# lt3652.net
KiCad netlist of a schematic drawn in EAGLE
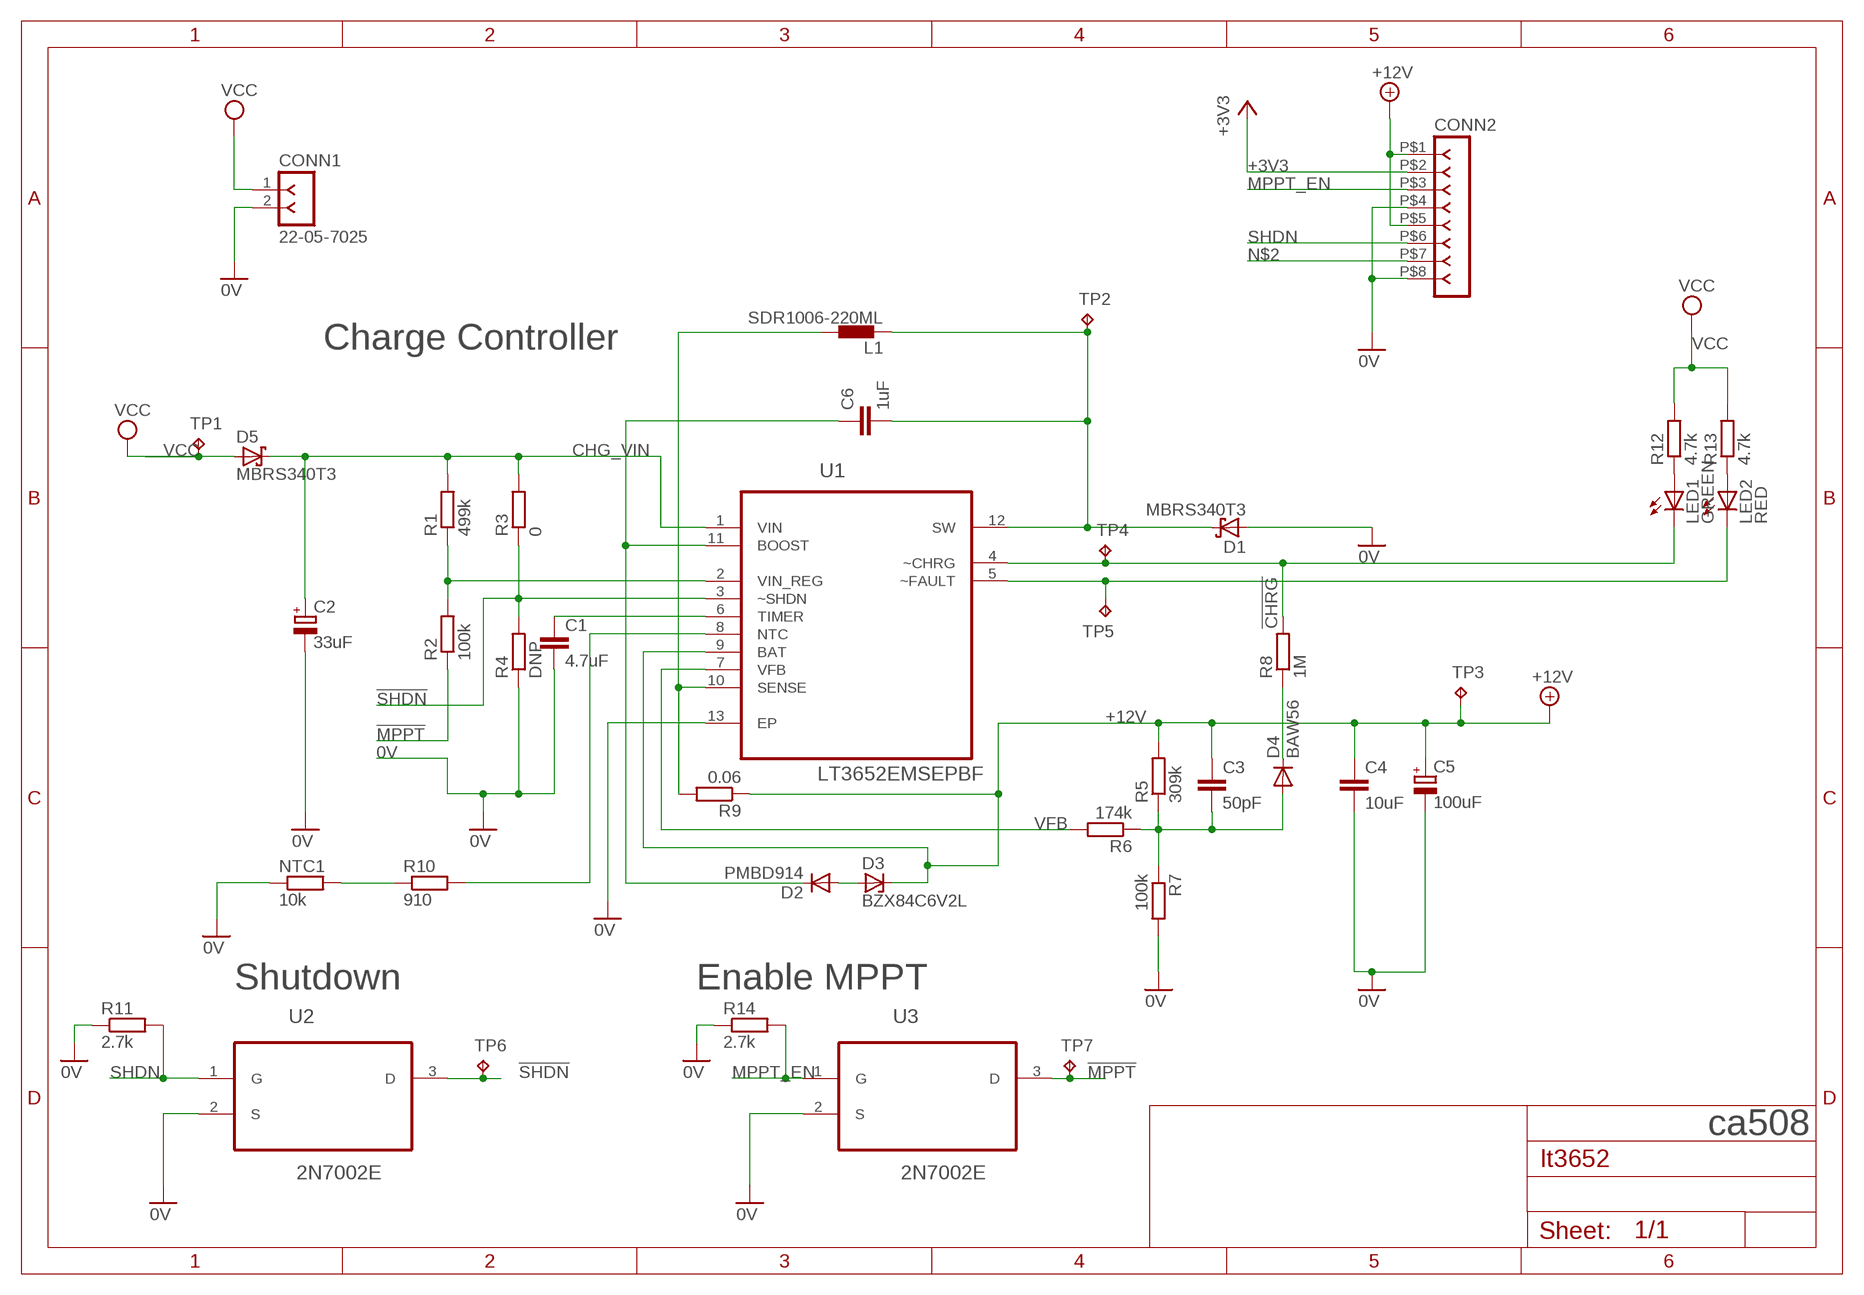
[diagram p0: schematic, sheet 1]

(export (version "E")
  (design (tool "Eeschema 10.0.6"))
  (components
    (comp (ref "C1")
      (value "4.7uF")
      (footprint "eagle-import:C1206")
      (libsource (lib "eagle-import") (part "C-EUC1206"))
    )
    (comp (ref "C2")
      (value "33uF")
      (footprint "eagle-import:PANASONIC_D")
      (libsource (lib "eagle-import") (part "CPOL-EUD"))
    )
    (comp (ref "C3")
      (value "50pF")
      (footprint "eagle-import:C0603")
      (libsource (lib "eagle-import") (part "C-EUC0603"))
    )
    (comp (ref "C4")
      (value "10uF")
      (footprint "eagle-import:C1206")
      (libsource (lib "eagle-import") (part "C-EUC1206"))
    )
    (comp (ref "C5")
      (value "100uF")
      (footprint "eagle-import:PANASONIC_F")
      (libsource (lib "eagle-import") (part "CPOL-EUF"))
    )
    (comp (ref "C6")
      (value "1uF")
      (footprint "eagle-import:C0805")
      (libsource (lib "eagle-import") (part "C-EUC0805"))
    )
    (comp (ref "CONN1")
      (value "22-05-7025")
      (footprint "eagle-import:22-05-7025")
      (libsource (lib "eagle-import") (part "22-05-7025"))
    )
    (comp (ref "CONN2")
      (value "39-28-1083")
      (footprint "eagle-import:39-28-1083")
      (libsource (lib "eagle-import") (part "39-28-1083"))
    )
    (comp (ref "D1")
      (value "MBRS340T3")
      (footprint "eagle-import:SMC")
      (libsource (lib "eagle-import") (part "MBRS30T34"))
    )
    (comp (ref "D2")
      (value "PMBD914")
      (footprint "eagle-import:SOT23")
      (libsource (lib "eagle-import") (part "DIODE"))
    )
    (comp (ref "D3")
      (value "BZX84C6V2L")
      (footprint "eagle-import:SOT23")
      (libsource (lib "eagle-import") (part "ZENER-DIODESOT23"))
    )
    (comp (ref "D4")
      (value "BAW56")
      (footprint "eagle-import:SOT23")
      (libsource (lib "eagle-import") (part "DIODE"))
    )
    (comp (ref "D5")
      (value "MBRS340T3")
      (footprint "eagle-import:SMC")
      (libsource (lib "eagle-import") (part "MBRS30T34"))
    )
    (comp (ref "L1")
      (value "SDR1006-220ML")
      (footprint "eagle-import:SDR1006")
      (libsource (lib "eagle-import") (part "SDR1006-XXXKL"))
    )
    (comp (ref "LED1")
      (value "GREEN")
      (footprint "eagle-import:CHIPLED_0603")
      (libsource (lib "eagle-import") (part "LEDCHIPLED_0603"))
    )
    (comp (ref "LED2")
      (value "RED")
      (footprint "eagle-import:CHIPLED_0603")
      (libsource (lib "eagle-import") (part "LEDCHIPLED_0603"))
    )
    (comp (ref "NTC1")
      (value "10k")
      (footprint "eagle-import:R0603")
      (libsource (lib "eagle-import") (part "R-EU_R0603"))
    )
    (comp (ref "R1")
      (value "499k")
      (footprint "eagle-import:R0603")
      (libsource (lib "eagle-import") (part "R-EU_R0603"))
    )
    (comp (ref "R2")
      (value "100k")
      (footprint "eagle-import:R0603")
      (libsource (lib "eagle-import") (part "R-EU_R0603"))
    )
    (comp (ref "R3")
      (value "0")
      (footprint "eagle-import:R0603")
      (libsource (lib "eagle-import") (part "R-EU_R0603"))
    )
    (comp (ref "R4")
      (value "DNP")
      (footprint "eagle-import:R0603")
      (libsource (lib "eagle-import") (part "R-EU_R0603"))
    )
    (comp (ref "R5")
      (value "309k")
      (footprint "eagle-import:R0805")
      (libsource (lib "eagle-import") (part "R-EU_R0805"))
    )
    (comp (ref "R6")
      (value "174k")
      (footprint "eagle-import:R0805")
      (libsource (lib "eagle-import") (part "R-EU_R0805"))
    )
    (comp (ref "R7")
      (value "100k")
      (footprint "eagle-import:R0805")
      (libsource (lib "eagle-import") (part "R-EU_R0805"))
    )
    (comp (ref "R8")
      (value "1M")
      (footprint "eagle-import:R0805")
      (libsource (lib "eagle-import") (part "R-EU_R0805"))
    )
    (comp (ref "R9")
      (value "0.06")
      (footprint "eagle-import:R2512")
      (libsource (lib "eagle-import") (part "R-EU_R2512"))
    )
    (comp (ref "R10")
      (value "910")
      (footprint "eagle-import:R0603")
      (libsource (lib "eagle-import") (part "R-EU_R0603"))
    )
    (comp (ref "R11")
      (value "2.7k")
      (footprint "eagle-import:R0603")
      (libsource (lib "eagle-import") (part "R-EU_R0603"))
    )
    (comp (ref "R12")
      (value "4.7k")
      (footprint "eagle-import:R0805")
      (libsource (lib "eagle-import") (part "R-EU_R0805"))
    )
    (comp (ref "R13")
      (value "4.7k")
      (footprint "eagle-import:R0805")
      (libsource (lib "eagle-import") (part "R-EU_R0805"))
    )
    (comp (ref "R14")
      (value "2.7k")
      (footprint "eagle-import:R0603")
      (libsource (lib "eagle-import") (part "R-EU_R0603"))
    )
    (comp (ref "TP1")
      (value "TPTP07R")
      (footprint "eagle-import:TP07R")
      (libsource (lib "eagle-import") (part "TPTP07R"))
    )
    (comp (ref "TP2")
      (value "TPTP07R")
      (footprint "eagle-import:TP07R")
      (libsource (lib "eagle-import") (part "TPTP07R"))
    )
    (comp (ref "TP3")
      (value "TPTP07R")
      (footprint "eagle-import:TP07R")
      (libsource (lib "eagle-import") (part "TPTP07R"))
    )
    (comp (ref "TP4")
      (value "TPTP07R")
      (footprint "eagle-import:TP07R")
      (libsource (lib "eagle-import") (part "TPTP07R"))
    )
    (comp (ref "TP5")
      (value "TPTP07R")
      (footprint "eagle-import:TP07R")
      (libsource (lib "eagle-import") (part "TPTP07R"))
    )
    (comp (ref "TP6")
      (value "TPTP07R")
      (footprint "eagle-import:TP07R")
      (libsource (lib "eagle-import") (part "TPTP07R"))
    )
    (comp (ref "TP7")
      (value "TPTP07R")
      (footprint "eagle-import:TP07R")
      (libsource (lib "eagle-import") (part "TPTP07R"))
    )
    (comp (ref "U1")
      (value "LT3652EMSEPBF")
      (footprint "eagle-import:SOP65P490X110-13N")
      (fields (field (name "MPN") "LT3652EMSE#PBF"))
      (libsource (lib "eagle-import") (part "LT3652EMSEPBF"))
    )
    (comp (ref "U2")
      (value "2N7002E")
      (footprint "eagle-import:SOT95P230X110-3N")
      (libsource (lib "eagle-import") (part "2N7002E"))
    )
    (comp (ref "U3")
      (value "2N7002E")
      (footprint "eagle-import:SOT95P230X110-3N")
      (libsource (lib "eagle-import") (part "2N7002E"))
    )
  )
  (nets
    (net (code "1") (name "+3V3") (class "Default")
      (node (ref "CONN2") (pin "P$2") (pinfunction "2_P$2") (pintype "passive"))
    )
    (net (code "2") (name "+12V") (class "Default")
      (node (ref "C3") (pin "1") (pinfunction "1_1") (pintype "passive"))
      (node (ref "C4") (pin "1") (pinfunction "1_1") (pintype "passive"))
      (node (ref "C5") (pin "+") (pinfunction "+_+") (pintype "passive"))
      (node (ref "CONN2") (pin "P$1") (pinfunction "1_P$1") (pintype "passive"))
      (node (ref "CONN2") (pin "P$5") (pinfunction "5_P$5") (pintype "passive"))
      (node (ref "D3") (pin "3") (pinfunction "C_3") (pintype "passive"))
      (node (ref "R5") (pin "2") (pinfunction "2_2") (pintype "passive"))
      (node (ref "R9") (pin "1") (pinfunction "1_1") (pintype "passive"))
      (node (ref "TP3") (pin "TP") (pinfunction "TP_TP") (pintype "input"))
      (node (ref "U1") (pin "9") (pinfunction "BAT_9") (pintype "power_in"))
    )
    (net (code "3") (name "/CHG_VIN") (class "Default")
      (node (ref "C2") (pin "+") (pinfunction "+_+") (pintype "passive"))
      (node (ref "D5") (pin "C") (pinfunction "C_C") (pintype "passive"))
      (node (ref "R1") (pin "2") (pinfunction "2_2") (pintype "passive"))
      (node (ref "R3") (pin "2") (pinfunction "2_2") (pintype "passive"))
      (node (ref "U1") (pin "1") (pinfunction "VIN_1") (pintype "power_in"))
    )
    (net (code "4") (name "/MPPT_EN") (class "Default")
      (node (ref "CONN2") (pin "P$3") (pinfunction "3_P$3") (pintype "passive"))
      (node (ref "R14") (pin "2") (pinfunction "2_2") (pintype "passive"))
      (node (ref "U3") (pin "1") (pinfunction "G_1") (pintype "passive"))
    )
    (net (code "5") (name "/N$2") (class "Default")
      (node (ref "CONN2") (pin "P$7") (pinfunction "7_P$7") (pintype "passive"))
    )
    (net (code "6") (name "/SHDN") (class "Default")
      (node (ref "CONN2") (pin "P$6") (pinfunction "6_P$6") (pintype "passive"))
      (node (ref "R11") (pin "2") (pinfunction "2_2") (pintype "passive"))
      (node (ref "U2") (pin "1") (pinfunction "G_1") (pintype "passive"))
    )
    (net (code "7") (name "/VFB") (class "Default")
      (node (ref "R6") (pin "2") (pinfunction "2_2") (pintype "passive"))
      (node (ref "U1") (pin "7") (pinfunction "VFB_7") (pintype "input"))
    )
    (net (code "8") (name "/~{CHRG}") (class "Default")
      (node (ref "LED1") (pin "C") (pinfunction "C_C") (pintype "passive"))
      (node (ref "R8") (pin "2") (pinfunction "2_2") (pintype "passive"))
      (node (ref "TP4") (pin "TP") (pinfunction "TP_TP") (pintype "input"))
      (node (ref "U1") (pin "4") (pinfunction "~{CHRG}_4") (pintype "output"))
    )
    (net (code "9") (name "/~{MPPT}") (class "Default")
      (node (ref "R2") (pin "1") (pinfunction "1_1") (pintype "passive"))
      (node (ref "TP7") (pin "TP") (pinfunction "TP_TP") (pintype "input"))
      (node (ref "U3") (pin "3") (pinfunction "D_3") (pintype "passive"))
    )
    (net (code "10") (name "/~{SHDN}") (class "Default")
      (node (ref "R3") (pin "1") (pinfunction "1_1") (pintype "passive"))
      (node (ref "R4") (pin "2") (pinfunction "2_2") (pintype "passive"))
      (node (ref "TP6") (pin "TP") (pinfunction "TP_TP") (pintype "input"))
      (node (ref "U1") (pin "3") (pinfunction "~{SHDN}_3") (pintype "input"))
      (node (ref "U2") (pin "3") (pinfunction "D_3") (pintype "passive"))
    )
    (net (code "11") (name "0V") (class "Default")
      (node (ref "C1") (pin "2") (pinfunction "2_2") (pintype "passive"))
      (node (ref "C2") (pin "-") (pinfunction "-_-") (pintype "passive"))
      (node (ref "C4") (pin "2") (pinfunction "2_2") (pintype "passive"))
      (node (ref "C5") (pin "-") (pinfunction "-_-") (pintype "passive"))
      (node (ref "CONN1") (pin "2") (pinfunction "2_2") (pintype "passive"))
      (node (ref "CONN2") (pin "P$4") (pinfunction "4_P$4") (pintype "passive"))
      (node (ref "CONN2") (pin "P$8") (pinfunction "8_P$8") (pintype "passive"))
      (node (ref "D1") (pin "A") (pinfunction "A_A") (pintype "passive"))
      (node (ref "NTC1") (pin "1") (pinfunction "1_1") (pintype "passive"))
      (node (ref "R11") (pin "1") (pinfunction "1_1") (pintype "passive"))
      (node (ref "R14") (pin "1") (pinfunction "1_1") (pintype "passive"))
      (node (ref "R4") (pin "1") (pinfunction "1_1") (pintype "passive"))
      (node (ref "R7") (pin "2") (pinfunction "2_2") (pintype "passive"))
      (node (ref "U1") (pin "13") (pinfunction "EP_13") (pintype "passive"))
      (node (ref "U2") (pin "2") (pinfunction "S_2") (pintype "passive"))
      (node (ref "U3") (pin "2") (pinfunction "S_2") (pintype "passive"))
    )
    (net (code "12") (name "Net-(D2-A)") (class "Default")
      (node (ref "D2") (pin "1") (pinfunction "A_1") (pintype "passive"))
      (node (ref "D3") (pin "1") (pinfunction "A_1") (pintype "passive"))
    )
    (net (code "13") (name "Net-(D2-C)") (class "Default")
      (node (ref "C6") (pin "1") (pinfunction "1_1") (pintype "passive"))
      (node (ref "D2") (pin "3") (pinfunction "C_3") (pintype "passive"))
      (node (ref "U1") (pin "11") (pinfunction "BOOST_11") (pintype "power_in"))
    )
    (net (code "14") (name "Net-(D4-A)") (class "Default")
      (node (ref "C3") (pin "2") (pinfunction "2_2") (pintype "passive"))
      (node (ref "D4") (pin "1") (pinfunction "A_1") (pintype "passive"))
      (node (ref "R5") (pin "1") (pinfunction "1_1") (pintype "passive"))
      (node (ref "R6") (pin "1") (pinfunction "1_1") (pintype "passive"))
      (node (ref "R7") (pin "1") (pinfunction "1_1") (pintype "passive"))
    )
    (net (code "15") (name "Net-(D4-C)") (class "Default")
      (node (ref "D4") (pin "3") (pinfunction "C_3") (pintype "passive"))
      (node (ref "R8") (pin "1") (pinfunction "1_1") (pintype "passive"))
    )
    (net (code "16") (name "Net-(L1-1)") (class "Default")
      (node (ref "C6") (pin "2") (pinfunction "2_2") (pintype "passive"))
      (node (ref "D1") (pin "C") (pinfunction "C_C") (pintype "passive"))
      (node (ref "L1") (pin "P$1") (pinfunction "1_P$1") (pintype "passive"))
      (node (ref "TP2") (pin "TP") (pinfunction "TP_TP") (pintype "input"))
      (node (ref "U1") (pin "12") (pinfunction "SW_12") (pintype "output"))
    )
    (net (code "17") (name "Net-(L1-2)") (class "Default")
      (node (ref "L1") (pin "P$2") (pinfunction "2_P$2") (pintype "passive"))
      (node (ref "R9") (pin "2") (pinfunction "2_2") (pintype "passive"))
      (node (ref "U1") (pin "10") (pinfunction "SENSE_10") (pintype "input"))
    )
    (net (code "18") (name "Net-(LED1-PadA)") (class "Default")
      (node (ref "LED1") (pin "A") (pinfunction "A_A") (pintype "passive"))
      (node (ref "R12") (pin "1") (pinfunction "1_1") (pintype "passive"))
    )
    (net (code "19") (name "Net-(LED2-PadA)") (class "Default")
      (node (ref "LED2") (pin "A") (pinfunction "A_A") (pintype "passive"))
      (node (ref "R13") (pin "1") (pinfunction "1_1") (pintype "passive"))
    )
    (net (code "20") (name "Net-(NTC1-Pad2)") (class "Default")
      (node (ref "NTC1") (pin "2") (pinfunction "2_2") (pintype "passive"))
      (node (ref "R10") (pin "1") (pinfunction "1_1") (pintype "passive"))
    )
    (net (code "21") (name "Net-(U1-NTC)") (class "Default")
      (node (ref "R10") (pin "2") (pinfunction "2_2") (pintype "passive"))
      (node (ref "U1") (pin "8") (pinfunction "NTC_8") (pintype "input"))
    )
    (net (code "22") (name "Net-(U1-TIMER)") (class "Default")
      (node (ref "C1") (pin "1") (pinfunction "1_1") (pintype "passive"))
      (node (ref "U1") (pin "6") (pinfunction "TIMER_6") (pintype "input"))
    )
    (net (code "23") (name "Net-(U1-VIN_REG)") (class "Default")
      (node (ref "R1") (pin "1") (pinfunction "1_1") (pintype "passive"))
      (node (ref "R2") (pin "2") (pinfunction "2_2") (pintype "passive"))
      (node (ref "U1") (pin "2") (pinfunction "VIN_REG_2") (pintype "input"))
    )
    (net (code "24") (name "Net-(U1-~{FAULT})") (class "Default")
      (node (ref "LED2") (pin "C") (pinfunction "C_C") (pintype "passive"))
      (node (ref "TP5") (pin "TP") (pinfunction "TP_TP") (pintype "input"))
      (node (ref "U1") (pin "5") (pinfunction "~{FAULT}_5") (pintype "output"))
    )
    (net (code "25") (name "VCC") (class "Default")
      (node (ref "CONN1") (pin "1") (pinfunction "1_1") (pintype "passive"))
      (node (ref "D5") (pin "A") (pinfunction "A_A") (pintype "passive"))
      (node (ref "R12") (pin "2") (pinfunction "2_2") (pintype "passive"))
      (node (ref "R13") (pin "2") (pinfunction "2_2") (pintype "passive"))
      (node (ref "TP1") (pin "TP") (pinfunction "TP_TP") (pintype "input"))
    )
  )
)
